# Olivia_LEDProject.net
KiCad netlist of a schematic drawn in Altium Designer
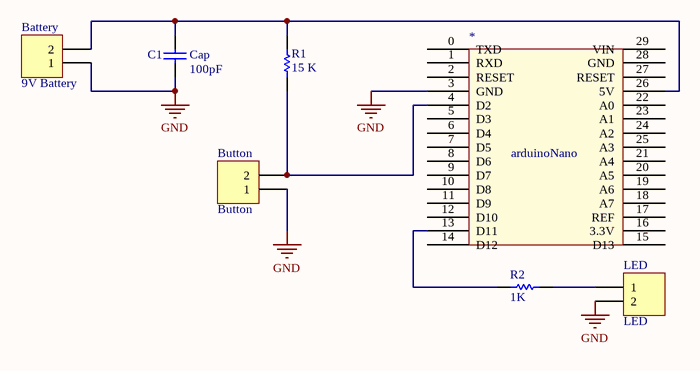
[diagram p0: Olivia_LEDProject.SchDoc]

(export (version "E")
  (design (tool "Eeschema 10.0.6"))
  (components
    (comp (ref "*")
      (value "arduinoNano")
      (footprint "Arduino nano")
      (libsource (lib "nanoArduino") (part "arduinoNano"))
    )
    (comp (ref "Battery")
      (value "9V Battery")
      (footprint "HDR1X2")
      (description "Header, 2-Pin")
      (fields (field (name "PUBLISHER") "Altium Limited"))
      (libsource (lib "") (part "Header 2_1"))
    )
    (comp (ref "Button")
      (value "Button")
      (footprint "HDR1X2")
      (description "Header, 2-Pin")
      (fields (field (name "PUBLISHER") "Altium Limited"))
      (libsource (lib "") (part "Header 2_1"))
    )
    (comp (ref "C1")
      (value "Cap")
      (footprint "RAD-0.3")
      (description "Capacitor")
      (fields (field (name "ALTIUM_VALUE") "100pF") (field (name "PUBLISHER") "Altium Limited"))
      (libsource (lib "Miscellaneous Devices") (part "Cap"))
    )
    (comp (ref "LED")
      (value "LED")
      (footprint "HDR1X2")
      (description "Header, 2-Pin")
      (fields (field (name "PUBLISHER") "Altium Limited"))
      (libsource (lib "Miscellaneous Connectors") (part "Header 2"))
    )
    (comp (ref "R1")
      (value "15 K")
      (footprint "YFDZ-MFJRY13-2_M")
      (fields
        (field (name "PARTNUMBER") "MFJRY13T52051K00")
        (field (name "MANUFACTURER") "YingFa Electronics")
      )
      (libsource (lib "Altium Content Vault") (part "YFDZ-RES-2"))
    )
    (comp (ref "R2")
      (value "1K")
      (footprint "YFDZ-MFJRY13-2_M")
      (fields
        (field (name "PARTNUMBER") "MFJRY13T52051K00")
        (field (name "MANUFACTURER") "YingFa Electronics")
      )
      (libsource (lib "Altium Content Vault") (part "YFDZ-RES-2"))
    )
  )
  (nets
    (net (code "1") (name "GND") (class "Default")
      (node (ref "*") (pin "3") (pinfunction "GND_3") (pintype "passive"))
      (node (ref "Battery") (pin "1") (pinfunction "1_1") (pintype "passive"))
      (node (ref "Button") (pin "1") (pinfunction "1_1") (pintype "passive"))
      (node (ref "C1") (pin "2") (pinfunction "2_2") (pintype "passive"))
      (node (ref "LED") (pin "2") (pinfunction "2_2") (pintype "passive"))
    )
    (net (code "2") (name "Net-(*-5V)") (class "Default")
      (node (ref "*") (pin "26") (pinfunction "5V_26") (pintype "passive"))
      (node (ref "Battery") (pin "2") (pinfunction "2_2") (pintype "passive"))
      (node (ref "C1") (pin "1") (pinfunction "1_1") (pintype "passive"))
      (node (ref "R1") (pin "2") (pinfunction "2_2") (pintype "passive"))
    )
    (net (code "3") (name "Net-(*-D2)") (class "Default")
      (node (ref "*") (pin "4") (pinfunction "D2_4") (pintype "passive"))
      (node (ref "Button") (pin "2") (pinfunction "2_2") (pintype "passive"))
      (node (ref "R1") (pin "1") (pinfunction "1_1") (pintype "passive"))
    )
    (net (code "4") (name "Net-(*-D11)") (class "Default")
      (node (ref "*") (pin "13") (pinfunction "D11_13") (pintype "passive"))
      (node (ref "R2") (pin "2") (pinfunction "2_2") (pintype "passive"))
    )
    (net (code "5") (name "Net-(LED-Pad1)") (class "Default")
      (node (ref "LED") (pin "1") (pinfunction "1_1") (pintype "passive"))
      (node (ref "R2") (pin "1") (pinfunction "1_1") (pintype "passive"))
    )
    (net (code "6") (name "unconnected-(*-3.3V-Pad16)") (class "Default")
      (node (ref "*") (pin "16") (pinfunction "3.3V_16") (pintype "passive"))
    )
    (net (code "7") (name "unconnected-(*-A0-Pad22)") (class "Default")
      (node (ref "*") (pin "22") (pinfunction "A0_22") (pintype "passive"))
    )
    (net (code "8") (name "unconnected-(*-A1-Pad23)") (class "Default")
      (node (ref "*") (pin "23") (pinfunction "A1_23") (pintype "passive"))
    )
    (net (code "9") (name "unconnected-(*-A2-Pad24)") (class "Default")
      (node (ref "*") (pin "24") (pinfunction "A2_24") (pintype "passive"))
    )
    (net (code "10") (name "unconnected-(*-A3-Pad25)") (class "Default")
      (node (ref "*") (pin "25") (pinfunction "A3_25") (pintype "passive"))
    )
    (net (code "11") (name "unconnected-(*-A4-Pad21)") (class "Default")
      (node (ref "*") (pin "21") (pinfunction "A4_21") (pintype "passive"))
    )
    (net (code "12") (name "unconnected-(*-A5-Pad20)") (class "Default")
      (node (ref "*") (pin "20") (pinfunction "A5_20") (pintype "passive"))
    )
    (net (code "13") (name "unconnected-(*-A6-Pad19)") (class "Default")
      (node (ref "*") (pin "19") (pinfunction "A6_19") (pintype "passive"))
    )
    (net (code "14") (name "unconnected-(*-A7-Pad18)") (class "Default")
      (node (ref "*") (pin "18") (pinfunction "A7_18") (pintype "passive"))
    )
    (net (code "15") (name "unconnected-(*-D3-Pad5)") (class "Default")
      (node (ref "*") (pin "5") (pinfunction "D3_5") (pintype "passive"))
    )
    (net (code "16") (name "unconnected-(*-D4-Pad6)") (class "Default")
      (node (ref "*") (pin "6") (pinfunction "D4_6") (pintype "passive"))
    )
    (net (code "17") (name "unconnected-(*-D5-Pad7)") (class "Default")
      (node (ref "*") (pin "7") (pinfunction "D5_7") (pintype "passive"))
    )
    (net (code "18") (name "unconnected-(*-D6-Pad8)") (class "Default")
      (node (ref "*") (pin "8") (pinfunction "D6_8") (pintype "passive"))
    )
    (net (code "19") (name "unconnected-(*-D7-Pad9)") (class "Default")
      (node (ref "*") (pin "9") (pinfunction "D7_9") (pintype "passive"))
    )
    (net (code "20") (name "unconnected-(*-D8-Pad10)") (class "Default")
      (node (ref "*") (pin "10") (pinfunction "D8_10") (pintype "passive"))
    )
    (net (code "21") (name "unconnected-(*-D9-Pad11)") (class "Default")
      (node (ref "*") (pin "11") (pinfunction "D9_11") (pintype "passive"))
    )
    (net (code "22") (name "unconnected-(*-D10-Pad12)") (class "Default")
      (node (ref "*") (pin "12") (pinfunction "D10_12") (pintype "passive"))
    )
    (net (code "23") (name "unconnected-(*-D12-Pad14)") (class "Default")
      (node (ref "*") (pin "14") (pinfunction "D12_14") (pintype "passive"))
    )
    (net (code "24") (name "unconnected-(*-D13-Pad15)") (class "Default")
      (node (ref "*") (pin "15") (pinfunction "D13_15") (pintype "passive"))
    )
    (net (code "25") (name "unconnected-(*-GND-Pad28)") (class "Default")
      (node (ref "*") (pin "28") (pinfunction "GND_28") (pintype "passive"))
    )
    (net (code "26") (name "unconnected-(*-REF-Pad17)") (class "Default")
      (node (ref "*") (pin "17") (pinfunction "REF_17") (pintype "passive"))
    )
    (net (code "27") (name "unconnected-(*-RESET-Pad2)") (class "Default")
      (node (ref "*") (pin "2") (pinfunction "RESET_2") (pintype "passive"))
    )
    (net (code "28") (name "unconnected-(*-RESET-Pad27)") (class "Default")
      (node (ref "*") (pin "27") (pinfunction "RESET_27") (pintype "passive"))
    )
    (net (code "29") (name "unconnected-(*-RXD-Pad1)") (class "Default")
      (node (ref "*") (pin "1") (pinfunction "RXD_1") (pintype "passive"))
    )
    (net (code "30") (name "unconnected-(*-TXD-Pad0)") (class "Default")
      (node (ref "*") (pin "0") (pinfunction "TXD_0") (pintype "passive"))
    )
    (net (code "31") (name "unconnected-(*-VIN-Pad29)") (class "Default")
      (node (ref "*") (pin "29") (pinfunction "VIN_29") (pintype "passive"))
    )
  )
)
